# V3.net
KiCad netlist of a schematic drawn in Altium Designer
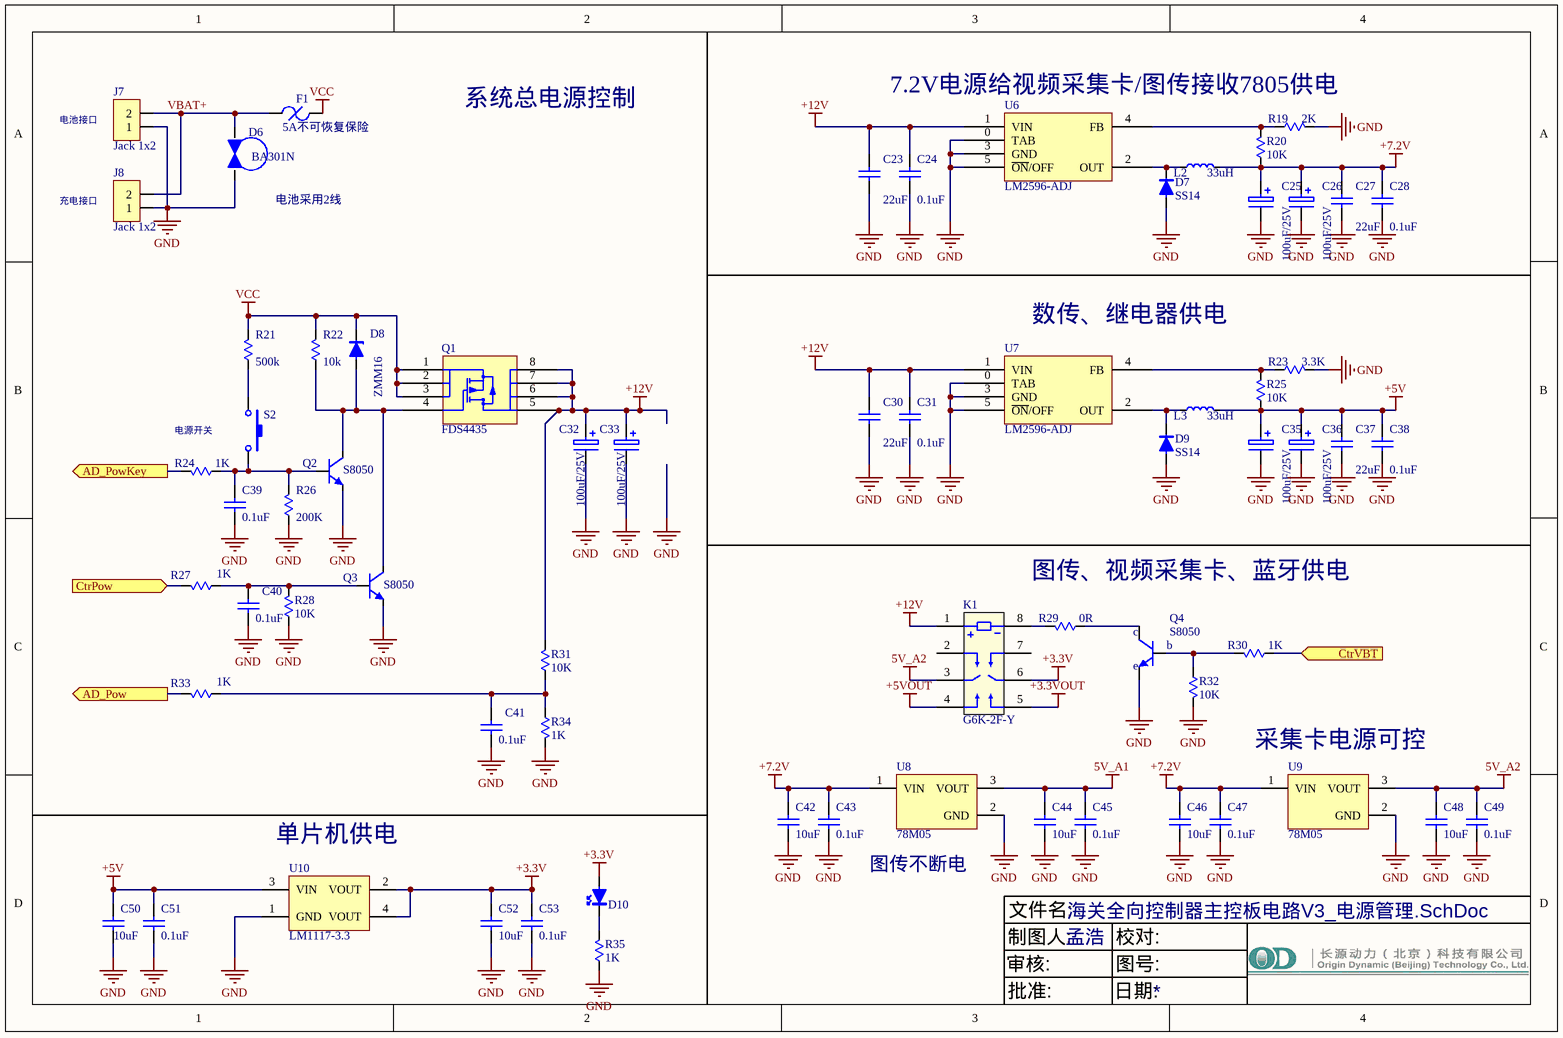
[diagram p0: 海关全向控制器主控板电路V3_电源管理.SchDoc]

(export (version "E")
  (design (tool "Eeschema 10.0.6"))
  (components
    (comp (ref "C23")
      (value "22uF")
      (footprint "C1210")
      (description "CAP")
      (fields (field (name "PUBLISHER") "Altium Limited"))
      (libsource (lib "Passive Components Class") (part "CAP"))
    )
    (comp (ref "C24")
      (value "0.1uF")
      (footprint "C0805")
      (description "CAP")
      (fields (field (name "PUBLISHER") "Altium Limited"))
      (libsource (lib "Passive Components Class") (part "CAP"))
    )
    (comp (ref "C25")
      (value "100uF/25V")
      (footprint "C7343")
      (description "Electrolytic Capacitor")
      (libsource (lib "*") (part "ELECTRO"))
    )
    (comp (ref "C26")
      (value "100uF/25V")
      (footprint "C7343")
      (description "Electrolytic Capacitor")
      (libsource (lib "*") (part "ELECTRO"))
    )
    (comp (ref "C27")
      (value "22uF")
      (footprint "C1210")
      (description "CAP")
      (fields (field (name "PUBLISHER") "Altium Limited"))
      (libsource (lib "Passive Components Class") (part "CAP"))
    )
    (comp (ref "C28")
      (value "0.1uF")
      (footprint "C0805")
      (description "CAP")
      (fields (field (name "PUBLISHER") "Altium Limited"))
      (libsource (lib "Passive Components Class") (part "CAP"))
    )
    (comp (ref "C30")
      (value "22uF")
      (footprint "C1210")
      (description "CAP")
      (fields (field (name "PUBLISHER") "Altium Limited"))
      (libsource (lib "Passive Components Class") (part "CAP"))
    )
    (comp (ref "C31")
      (value "0.1uF")
      (footprint "C0805")
      (description "CAP")
      (fields (field (name "PUBLISHER") "Altium Limited"))
      (libsource (lib "Passive Components Class") (part "CAP"))
    )
    (comp (ref "C32") (value "100uF/25V") (footprint "C7343") (libsource (lib "RLCYDF") (part "Cap Poll")))
    (comp (ref "C33") (value "100uF/25V") (footprint "C7343") (libsource (lib "RLCYDF") (part "Cap Poll")))
    (comp (ref "C35")
      (value "100uF/25V")
      (footprint "C7343")
      (description "Electrolytic Capacitor")
      (libsource (lib "*") (part "ELECTRO"))
    )
    (comp (ref "C36")
      (value "100uF/25V")
      (footprint "C7343")
      (description "Electrolytic Capacitor")
      (libsource (lib "*") (part "ELECTRO"))
    )
    (comp (ref "C37")
      (value "22uF")
      (footprint "C1210")
      (description "CAP")
      (fields (field (name "PUBLISHER") "Altium Limited"))
      (libsource (lib "Passive Components Class") (part "CAP"))
    )
    (comp (ref "C38")
      (value "0.1uF")
      (footprint "C0805")
      (description "CAP")
      (fields (field (name "PUBLISHER") "Altium Limited"))
      (libsource (lib "Passive Components Class") (part "CAP"))
    )
    (comp (ref "C39")
      (value "0.1uF")
      (footprint "C0805")
      (description "CAP")
      (fields (field (name "PUBLISHER") "Altium Limited"))
      (libsource (lib "Passive Components Class") (part "CAP"))
    )
    (comp (ref "C40")
      (value "0.1uF")
      (footprint "C0805")
      (description "CAP")
      (fields (field (name "PUBLISHER") "Altium Limited"))
      (libsource (lib "Passive Components Class") (part "CAP"))
    )
    (comp (ref "C41")
      (value "0.1uF")
      (footprint "C0805")
      (description "CAP")
      (fields (field (name "PUBLISHER") "Altium Limited"))
      (libsource (lib "Passive Components Class") (part "CAP"))
    )
    (comp (ref "C42")
      (value "10uF")
      (footprint "C0805")
      (description "CAP")
      (fields (field (name "PUBLISHER") "Altium Limited"))
      (libsource (lib "Passive Components Class") (part "CAP"))
    )
    (comp (ref "C43")
      (value "0.1uF")
      (footprint "C0805")
      (description "CAP")
      (fields (field (name "PUBLISHER") "Altium Limited"))
      (libsource (lib "Passive Components Class") (part "CAP"))
    )
    (comp (ref "C44")
      (value "10uF")
      (footprint "C0805")
      (description "CAP")
      (fields (field (name "PUBLISHER") "Altium Limited"))
      (libsource (lib "Passive Components Class") (part "CAP"))
    )
    (comp (ref "C45")
      (value "0.1uF")
      (footprint "C0805")
      (description "CAP")
      (fields (field (name "PUBLISHER") "Altium Limited"))
      (libsource (lib "Passive Components Class") (part "CAP"))
    )
    (comp (ref "C46")
      (value "10uF")
      (footprint "C0805")
      (description "CAP")
      (fields (field (name "PUBLISHER") "Altium Limited"))
      (libsource (lib "Passive Components Class") (part "CAP"))
    )
    (comp (ref "C47")
      (value "0.1uF")
      (footprint "C0805")
      (description "CAP")
      (fields (field (name "PUBLISHER") "Altium Limited"))
      (libsource (lib "Passive Components Class") (part "CAP"))
    )
    (comp (ref "C48")
      (value "10uF")
      (footprint "C0805")
      (description "CAP")
      (fields (field (name "PUBLISHER") "Altium Limited"))
      (libsource (lib "Passive Components Class") (part "CAP"))
    )
    (comp (ref "C49")
      (value "0.1uF")
      (footprint "C0805")
      (description "CAP")
      (fields (field (name "PUBLISHER") "Altium Limited"))
      (libsource (lib "Passive Components Class") (part "CAP"))
    )
    (comp (ref "C50")
      (value "10uF")
      (footprint "C0805")
      (description "CAP")
      (fields (field (name "PUBLISHER") "Altium Limited"))
      (libsource (lib "Passive Components Class") (part "CAP"))
    )
    (comp (ref "C51")
      (value "0.1uF")
      (footprint "C0805")
      (description "CAP")
      (fields (field (name "PUBLISHER") "Altium Limited"))
      (libsource (lib "Passive Components Class") (part "CAP"))
    )
    (comp (ref "C52")
      (value "10uF")
      (footprint "C0805")
      (description "CAP")
      (fields (field (name "PUBLISHER") "Altium Limited"))
      (libsource (lib "Passive Components Class") (part "CAP"))
    )
    (comp (ref "C53")
      (value "0.1uF")
      (footprint "C0805")
      (description "CAP")
      (fields (field (name "PUBLISHER") "Altium Limited"))
      (libsource (lib "Passive Components Class") (part "CAP"))
    )
    (comp (ref "D6") (value "BA301N") (footprint "BA301N") (libsource (lib "MhSchlib") (part "BA301N")))
    (comp (ref "D7")
      (value "SS14")
      (footprint "SMA")
      (description "Silicon Epitaxial Planar Diodes")
      (libsource (lib "RLCYDF") (part "Diode-Switch"))
    )
    (comp (ref "D8")
      (value "ZMM16")
      (footprint "SOD-80-S")
      (description "Small Signal Zener Diodes")
      (libsource (lib "Passive Components Class") (part "DIODE-ZENER"))
    )
    (comp (ref "D9")
      (value "SS14")
      (footprint "SMA")
      (description "Silicon Epitaxial Planar Diodes")
      (libsource (lib "RLCYDF") (part "Diode-Switch"))
    )
    (comp (ref "D10")
      (value "LED")
      (footprint "LED0603")
      (libsource (lib "Passive Components Class") (part "LED"))
    )
    (comp (ref "F1") (value "5A不可恢复保险") (footprint "F1808") (libsource (lib "RLCYDF") (part "Fuse2")))
    (comp (ref "J7")
      (value "Jack 1x2")
      (footprint "35363-0260")
      (description "插座")
      (libsource (lib "Connector") (part "Jack 1x2"))
    )
    (comp (ref "J8")
      (value "Jack 1x2")
      (footprint "35363-0260")
      (description "插座")
      (libsource (lib "Connector") (part "Jack 1x2"))
    )
    (comp (ref "K1")
      (value "G6K-2F-Y")
      (footprint "G6K-2F-Y")
      (libsource (lib "海关全向本体电路板V3") (part "G6K-2F-Y"))
    )
    (comp (ref "L2")
      (value "33uH")
      (footprint "L6.6*7.1mm")
      (description "INDUCTOR")
      (fields (field (name "PUBLISHER") "Altium Limited"))
      (libsource (lib "Passive Components Class") (part "INDUCTOR"))
    )
    (comp (ref "L3")
      (value "33uH")
      (footprint "L6.6*7.1mm")
      (description "INDUCTOR")
      (fields (field (name "PUBLISHER") "Altium Limited"))
      (libsource (lib "Passive Components Class") (part "INDUCTOR"))
    )
    (comp (ref "Q1") (value "FDS4435") (footprint "SO8") (libsource (lib "OmniDirCtr") (part "FDS4435")))
    (comp (ref "Q2")
      (value "S8050")
      (footprint "SOT-23")
      (description "NPN General Purpose Amplifier")
      (fields (field (name "PUBLISHER") "Altium Limited"))
      (libsource (lib "Bdmc4810") (part "NPN"))
    )
    (comp (ref "Q3")
      (value "S8050")
      (footprint "SOT-23")
      (description "NPN General Purpose Amplifier")
      (fields (field (name "PUBLISHER") "Altium Limited"))
      (libsource (lib "Bdmc4810") (part "NPN"))
    )
    (comp (ref "Q4")
      (value "S8050")
      (footprint "SOT-23")
      (description "NPN triode, 0.5A Max")
      (libsource (lib "RLCYDF") (part "S8050"))
    )
    (comp (ref "R19")
      (value "2K")
      (footprint "R0805")
      (description "Resistor")
      (fields (field (name "PUBLISHER") "Altium Limited"))
      (libsource (lib "Passive Components Class") (part "RES"))
    )
    (comp (ref "R20")
      (value "10K")
      (footprint "R0805")
      (description "Resistor")
      (fields (field (name "PUBLISHER") "Altium Limited"))
      (libsource (lib "Passive Components Class") (part "RES"))
    )
    (comp (ref "R21")
      (value "500k")
      (footprint "R0805")
      (description "Resistor")
      (fields (field (name "PUBLISHER") "Altium Limited"))
      (libsource (lib "Temp") (part "Res"))
    )
    (comp (ref "R22")
      (value "10k")
      (footprint "R0805")
      (description "Resistor")
      (fields (field (name "PUBLISHER") "Altium Limited"))
      (libsource (lib "Temp") (part "Res"))
    )
    (comp (ref "R23")
      (value "3.3K")
      (footprint "R0805")
      (description "Resistor")
      (fields (field (name "PUBLISHER") "Altium Limited"))
      (libsource (lib "Passive Components Class") (part "RES"))
    )
    (comp (ref "R24")
      (value "1K")
      (footprint "R0805")
      (description "Resistor")
      (fields (field (name "PUBLISHER") "Altium Limited"))
      (libsource (lib "Temp") (part "Res"))
    )
    (comp (ref "R25")
      (value "10K")
      (footprint "R0805")
      (description "Resistor")
      (fields (field (name "PUBLISHER") "Altium Limited"))
      (libsource (lib "Passive Components Class") (part "RES"))
    )
    (comp (ref "R26")
      (value "200K")
      (footprint "R0805")
      (description "Resistor")
      (fields (field (name "PUBLISHER") "Altium Limited"))
      (libsource (lib "Temp") (part "Res"))
    )
    (comp (ref "R27")
      (value "1K")
      (footprint "R0805")
      (description "Resistor")
      (fields (field (name "PUBLISHER") "Altium Limited"))
      (libsource (lib "Temp") (part "Res"))
    )
    (comp (ref "R28")
      (value "10K")
      (footprint "R0805")
      (description "Resistor")
      (fields (field (name "PUBLISHER") "Altium Limited"))
      (libsource (lib "Temp") (part "Res"))
    )
    (comp (ref "R29")
      (value "0R")
      (footprint "R0805")
      (description "Resistor")
      (fields (field (name "PUBLISHER") "Altium Limited"))
      (libsource (lib "Passive Components Class") (part "RES"))
    )
    (comp (ref "R30")
      (value "1K")
      (footprint "R0805")
      (description "Resistor")
      (fields (field (name "PUBLISHER") "Altium Limited"))
      (libsource (lib "Passive Components Class") (part "RES"))
    )
    (comp (ref "R31")
      (value "10K")
      (footprint "R0805")
      (description "Resistor")
      (fields (field (name "PUBLISHER") "Altium Limited"))
      (libsource (lib "Temp") (part "Res"))
    )
    (comp (ref "R32")
      (value "10K")
      (footprint "R0805")
      (description "Resistor")
      (fields (field (name "PUBLISHER") "Altium Limited"))
      (libsource (lib "Passive Components Class") (part "RES"))
    )
    (comp (ref "R33")
      (value "1K")
      (footprint "R0805")
      (description "Resistor")
      (fields (field (name "PUBLISHER") "Altium Limited"))
      (libsource (lib "Temp") (part "Res"))
    )
    (comp (ref "R34")
      (value "1K")
      (footprint "R0805")
      (description "Resistor")
      (fields (field (name "PUBLISHER") "Altium Limited"))
      (libsource (lib "Temp") (part "Res"))
    )
    (comp (ref "R35")
      (value "1K")
      (footprint "R0805")
      (description "Resistor")
      (fields (field (name "PUBLISHER") "Altium Limited"))
      (libsource (lib "UP-Robot") (part "Res"))
    )
    (comp (ref "S2")
      (value "SW-PB")
      (footprint "ZH-2AWD")
      (description "Switch")
      (fields (field (name "PUBLISHER") "Altium Limited"))
      (libsource (lib "海关全向控制器主控板V3") (part "SW-PB"))
    )
    (comp (ref "U6")
      (value "LM2596-ADJ")
      (footprint "TO-263-5")
      (description "LM2596-5;LM2576-5")
      (libsource (lib "chip") (part "LM25x6-5"))
    )
    (comp (ref "U7")
      (value "LM2596-ADJ")
      (footprint "TO-263-5")
      (description "LM2596-5;LM2576-5")
      (libsource (lib "chip") (part "LM25x6-5"))
    )
    (comp (ref "U8") (value "78M05") (footprint "TO-252") (libsource (lib "chip") (part "78M05")))
    (comp (ref "U9") (value "78M05") (footprint "TO-252") (libsource (lib "chip") (part "78M05")))
    (comp (ref "U10")
      (value "LM1117-3.3")
      (footprint "SOT-223")
      (description "800mA Linear Voltage Regulator")
      (libsource (lib "chip") (part "LM1117"))
    )
  )
  (nets
    (net (code "1") (name "+3.3V") (class "Default")
      (node (ref "C52") (pin "1") (pinfunction "1_1") (pintype "passive"))
      (node (ref "C53") (pin "2") (pinfunction "2_2") (pintype "passive"))
      (node (ref "D10") (pin "1") (pinfunction "A_1") (pintype "passive"))
      (node (ref "K1") (pin "6") (pinfunction "6_6") (pintype "passive"))
      (node (ref "U10") (pin "2") (pinfunction "VOUT_2") (pintype "passive"))
      (node (ref "U10") (pin "4") (pinfunction "VOUT_4") (pintype "passive"))
    )
    (net (code "2") (name "+3.3VOUT") (class "Default")
      (node (ref "K1") (pin "5") (pinfunction "5_5") (pintype "passive"))
    )
    (net (code "3") (name "+5V") (class "Default")
      (node (ref "C35") (pin "1") (pinfunction "1_1") (pintype "passive"))
      (node (ref "C36") (pin "1") (pinfunction "1_1") (pintype "passive"))
      (node (ref "C37") (pin "1") (pinfunction "1_1") (pintype "passive"))
      (node (ref "C38") (pin "2") (pinfunction "2_2") (pintype "passive"))
      (node (ref "C50") (pin "1") (pinfunction "1_1") (pintype "passive"))
      (node (ref "C51") (pin "2") (pinfunction "2_2") (pintype "passive"))
      (node (ref "L3") (pin "2") (pinfunction "2_2") (pintype "passive"))
      (node (ref "R25") (pin "1") (pinfunction "1_1") (pintype "passive"))
      (node (ref "U10") (pin "3") (pinfunction "VIN_3") (pintype "passive"))
    )
    (net (code "4") (name "+5VOUT") (class "Default")
      (node (ref "K1") (pin "4") (pinfunction "4_4") (pintype "passive"))
    )
    (net (code "5") (name "+7.2V") (class "Default")
      (node (ref "C25") (pin "1") (pinfunction "1_1") (pintype "passive"))
      (node (ref "C26") (pin "1") (pinfunction "1_1") (pintype "passive"))
      (node (ref "C27") (pin "1") (pinfunction "1_1") (pintype "passive"))
      (node (ref "C28") (pin "2") (pinfunction "2_2") (pintype "passive"))
      (node (ref "C42") (pin "1") (pinfunction "1_1") (pintype "passive"))
      (node (ref "C43") (pin "2") (pinfunction "2_2") (pintype "passive"))
      (node (ref "C46") (pin "1") (pinfunction "1_1") (pintype "passive"))
      (node (ref "C47") (pin "2") (pinfunction "2_2") (pintype "passive"))
      (node (ref "L2") (pin "2") (pinfunction "2_2") (pintype "passive"))
      (node (ref "R20") (pin "1") (pinfunction "1_1") (pintype "passive"))
      (node (ref "U8") (pin "1") (pinfunction "VIN_1") (pintype "passive"))
      (node (ref "U9") (pin "1") (pinfunction "VIN_1") (pintype "passive"))
    )
    (net (code "6") (name "+12V") (class "Default")
      (node (ref "C23") (pin "1") (pinfunction "1_1") (pintype "passive"))
      (node (ref "C24") (pin "2") (pinfunction "2_2") (pintype "passive"))
      (node (ref "C30") (pin "1") (pinfunction "1_1") (pintype "passive"))
      (node (ref "C31") (pin "2") (pinfunction "2_2") (pintype "passive"))
      (node (ref "C32") (pin "1") (pinfunction "1_1") (pintype "passive"))
      (node (ref "C33") (pin "1") (pinfunction "1_1") (pintype "passive"))
      (node (ref "K1") (pin "1") (pinfunction "1_1") (pintype "passive"))
      (node (ref "Q1") (pin "5") (pintype "passive"))
      (node (ref "Q1") (pin "6") (pintype "passive"))
      (node (ref "Q1") (pin "7") (pintype "passive"))
      (node (ref "Q1") (pin "8") (pintype "passive"))
      (node (ref "R31") (pin "1") (pinfunction "1_1") (pintype "passive"))
      (node (ref "U6") (pin "1") (pinfunction "VIN_1") (pintype "passive"))
      (node (ref "U7") (pin "1") (pinfunction "VIN_1") (pintype "passive"))
    )
    (net (code "7") (name "/AD_Pow") (class "Default")
      (node (ref "R33") (pin "1") (pinfunction "1_1") (pintype "passive"))
    )
    (net (code "8") (name "/AD_PowKey") (class "Default")
      (node (ref "R24") (pin "1") (pinfunction "1_1") (pintype "passive"))
    )
    (net (code "9") (name "/CtrPow") (class "Default")
      (node (ref "R27") (pin "1") (pinfunction "1_1") (pintype "passive"))
    )
    (net (code "10") (name "/CtrVBT") (class "Default")
      (node (ref "R30") (pin "1") (pinfunction "1_1") (pintype "passive"))
    )
    (net (code "11") (name "/VBAT+") (class "Default")
      (node (ref "D6") (pin "1") (pinfunction "1_1") (pintype "passive"))
      (node (ref "F1") (pin "1") (pinfunction "1_1") (pintype "passive"))
      (node (ref "J7") (pin "2") (pinfunction "2_2") (pintype "passive"))
      (node (ref "J8") (pin "2") (pinfunction "2_2") (pintype "passive"))
    )
    (net (code "12") (name "5V_A1") (class "Default")
      (node (ref "C44") (pin "1") (pinfunction "1_1") (pintype "passive"))
      (node (ref "C45") (pin "2") (pinfunction "2_2") (pintype "passive"))
      (node (ref "U8") (pin "3") (pinfunction "VOUT_3") (pintype "passive"))
    )
    (net (code "13") (name "5V_A2") (class "Default")
      (node (ref "C48") (pin "1") (pinfunction "1_1") (pintype "passive"))
      (node (ref "C49") (pin "2") (pinfunction "2_2") (pintype "passive"))
      (node (ref "K1") (pin "3") (pinfunction "3_3") (pintype "passive"))
      (node (ref "U9") (pin "3") (pinfunction "VOUT_3") (pintype "passive"))
    )
    (net (code "14") (name "GND") (class "Default")
      (node (ref "C23") (pin "2") (pinfunction "2_2") (pintype "passive"))
      (node (ref "C24") (pin "1") (pinfunction "1_1") (pintype "passive"))
      (node (ref "C25") (pin "2") (pinfunction "2_2") (pintype "passive"))
      (node (ref "C26") (pin "2") (pinfunction "2_2") (pintype "passive"))
      (node (ref "C27") (pin "2") (pinfunction "2_2") (pintype "passive"))
      (node (ref "C28") (pin "1") (pinfunction "1_1") (pintype "passive"))
      (node (ref "C30") (pin "2") (pinfunction "2_2") (pintype "passive"))
      (node (ref "C31") (pin "1") (pinfunction "1_1") (pintype "passive"))
      (node (ref "C32") (pin "2") (pinfunction "2_2") (pintype "passive"))
      (node (ref "C33") (pin "2") (pinfunction "2_2") (pintype "passive"))
      (node (ref "C35") (pin "2") (pinfunction "2_2") (pintype "passive"))
      (node (ref "C36") (pin "2") (pinfunction "2_2") (pintype "passive"))
      (node (ref "C37") (pin "2") (pinfunction "2_2") (pintype "passive"))
      (node (ref "C38") (pin "1") (pinfunction "1_1") (pintype "passive"))
      (node (ref "C39") (pin "1") (pinfunction "1_1") (pintype "passive"))
      (node (ref "C40") (pin "1") (pinfunction "1_1") (pintype "passive"))
      (node (ref "C41") (pin "1") (pinfunction "1_1") (pintype "passive"))
      (node (ref "C42") (pin "2") (pinfunction "2_2") (pintype "passive"))
      (node (ref "C43") (pin "1") (pinfunction "1_1") (pintype "passive"))
      (node (ref "C44") (pin "2") (pinfunction "2_2") (pintype "passive"))
      (node (ref "C45") (pin "1") (pinfunction "1_1") (pintype "passive"))
      (node (ref "C46") (pin "2") (pinfunction "2_2") (pintype "passive"))
      (node (ref "C47") (pin "1") (pinfunction "1_1") (pintype "passive"))
      (node (ref "C48") (pin "2") (pinfunction "2_2") (pintype "passive"))
      (node (ref "C49") (pin "1") (pinfunction "1_1") (pintype "passive"))
      (node (ref "C50") (pin "2") (pinfunction "2_2") (pintype "passive"))
      (node (ref "C51") (pin "1") (pinfunction "1_1") (pintype "passive"))
      (node (ref "C52") (pin "2") (pinfunction "2_2") (pintype "passive"))
      (node (ref "C53") (pin "1") (pinfunction "1_1") (pintype "passive"))
      (node (ref "D6") (pin "2") (pinfunction "2_2") (pintype "passive"))
      (node (ref "D7") (pin "1") (pinfunction "A_1") (pintype "passive"))
      (node (ref "D9") (pin "1") (pinfunction "A_1") (pintype "passive"))
      (node (ref "J7") (pin "1") (pinfunction "1_1") (pintype "passive"))
      (node (ref "J8") (pin "1") (pinfunction "1_1") (pintype "passive"))
      (node (ref "Q2") (pin "2") (pinfunction "E_2") (pintype "passive"))
      (node (ref "Q3") (pin "2") (pinfunction "E_2") (pintype "passive"))
      (node (ref "Q4") (pin "2") (pinfunction "e_2") (pintype "passive"))
      (node (ref "R19") (pin "2") (pinfunction "2_2") (pintype "passive"))
      (node (ref "R23") (pin "2") (pinfunction "2_2") (pintype "passive"))
      (node (ref "R26") (pin "2") (pinfunction "2_2") (pintype "passive"))
      (node (ref "R28") (pin "2") (pinfunction "2_2") (pintype "passive"))
      (node (ref "R32") (pin "2") (pinfunction "2_2") (pintype "passive"))
      (node (ref "R34") (pin "1") (pinfunction "1_1") (pintype "passive"))
      (node (ref "R35") (pin "1") (pinfunction "1_1") (pintype "passive"))
      (node (ref "U10") (pin "1") (pinfunction "GND_1") (pintype "passive"))
      (node (ref "U6") (pin "0") (pinfunction "TAB_0") (pintype "passive"))
      (node (ref "U6") (pin "3") (pinfunction "GND_3") (pintype "passive"))
      (node (ref "U6") (pin "5") (pinfunction "~{ON}/OFF_5") (pintype "passive"))
      (node (ref "U7") (pin "0") (pinfunction "TAB_0") (pintype "passive"))
      (node (ref "U7") (pin "3") (pinfunction "GND_3") (pintype "passive"))
      (node (ref "U7") (pin "5") (pinfunction "~{ON}/OFF_5") (pintype "passive"))
      (node (ref "U8") (pin "2") (pinfunction "GND_2") (pintype "passive"))
      (node (ref "U9") (pin "2") (pinfunction "GND_2") (pintype "passive"))
    )
    (net (code "15") (name "Net-(C41-Pad2)") (class "Default")
      (node (ref "C41") (pin "2") (pinfunction "2_2") (pintype "passive"))
      (node (ref "R31") (pin "2") (pinfunction "2_2") (pintype "passive"))
      (node (ref "R33") (pin "2") (pinfunction "2_2") (pintype "passive"))
      (node (ref "R34") (pin "2") (pinfunction "2_2") (pintype "passive"))
    )
    (net (code "16") (name "Net-(D7-K)") (class "Default")
      (node (ref "D7") (pin "2") (pinfunction "K_2") (pintype "passive"))
      (node (ref "L2") (pin "1") (pinfunction "1_1") (pintype "passive"))
      (node (ref "U6") (pin "2") (pinfunction "OUT_2") (pintype "passive"))
    )
    (net (code "17") (name "Net-(D8-A)") (class "Default")
      (node (ref "D8") (pin "1") (pinfunction "A_1") (pintype "passive"))
      (node (ref "Q1") (pin "4") (pintype "passive"))
      (node (ref "Q2") (pin "3") (pinfunction "C_3") (pintype "passive"))
      (node (ref "Q3") (pin "3") (pinfunction "C_3") (pintype "passive"))
      (node (ref "R22") (pin "1") (pinfunction "1_1") (pintype "passive"))
    )
    (net (code "18") (name "Net-(D9-K)") (class "Default")
      (node (ref "D9") (pin "2") (pinfunction "K_2") (pintype "passive"))
      (node (ref "L3") (pin "1") (pinfunction "1_1") (pintype "passive"))
      (node (ref "U7") (pin "2") (pinfunction "OUT_2") (pintype "passive"))
    )
    (net (code "19") (name "Net-(D10-K)") (class "Default")
      (node (ref "D10") (pin "2") (pinfunction "K_2") (pintype "passive"))
      (node (ref "R35") (pin "2") (pinfunction "2_2") (pintype "passive"))
    )
    (net (code "20") (name "Net-(K1-Pad8)") (class "Default")
      (node (ref "K1") (pin "8") (pinfunction "8_8") (pintype "passive"))
      (node (ref "R29") (pin "2") (pinfunction "2_2") (pintype "passive"))
    )
    (net (code "21") (name "Net-(Q2-B)") (class "Default")
      (node (ref "C39") (pin "2") (pinfunction "2_2") (pintype "passive"))
      (node (ref "Q2") (pin "1") (pinfunction "B_1") (pintype "passive"))
      (node (ref "R24") (pin "2") (pinfunction "2_2") (pintype "passive"))
      (node (ref "R26") (pin "1") (pinfunction "1_1") (pintype "passive"))
      (node (ref "S2") (pin "2") (pinfunction "2_2") (pintype "passive"))
    )
    (net (code "22") (name "Net-(Q3-B)") (class "Default")
      (node (ref "C40") (pin "2") (pinfunction "2_2") (pintype "passive"))
      (node (ref "Q3") (pin "1") (pinfunction "B_1") (pintype "passive"))
      (node (ref "R27") (pin "2") (pinfunction "2_2") (pintype "passive"))
      (node (ref "R28") (pin "1") (pinfunction "1_1") (pintype "passive"))
    )
    (net (code "23") (name "Net-(Q4-b)") (class "Default")
      (node (ref "Q4") (pin "1") (pinfunction "b_1") (pintype "passive"))
      (node (ref "R30") (pin "2") (pinfunction "2_2") (pintype "passive"))
      (node (ref "R32") (pin "1") (pinfunction "1_1") (pintype "passive"))
    )
    (net (code "24") (name "Net-(Q4-c)") (class "Default")
      (node (ref "Q4") (pin "3") (pinfunction "c_3") (pintype "passive"))
      (node (ref "R29") (pin "1") (pinfunction "1_1") (pintype "passive"))
    )
    (net (code "25") (name "Net-(R21-Pad1)") (class "Default")
      (node (ref "R21") (pin "1") (pinfunction "1_1") (pintype "passive"))
      (node (ref "S2") (pin "1") (pinfunction "1_1") (pintype "passive"))
    )
    (net (code "26") (name "Net-(U6-FB)") (class "Default")
      (node (ref "R19") (pin "1") (pinfunction "1_1") (pintype "passive"))
      (node (ref "R20") (pin "2") (pinfunction "2_2") (pintype "passive"))
      (node (ref "U6") (pin "4") (pinfunction "FB_4") (pintype "passive"))
    )
    (net (code "27") (name "Net-(U7-FB)") (class "Default")
      (node (ref "R23") (pin "1") (pinfunction "1_1") (pintype "passive"))
      (node (ref "R25") (pin "2") (pinfunction "2_2") (pintype "passive"))
      (node (ref "U7") (pin "4") (pinfunction "FB_4") (pintype "passive"))
    )
    (net (code "28") (name "VCC") (class "Default")
      (node (ref "D8") (pin "2") (pinfunction "K_2") (pintype "passive"))
      (node (ref "F1") (pin "2") (pinfunction "2_2") (pintype "passive"))
      (node (ref "Q1") (pin "1") (pintype "passive"))
      (node (ref "Q1") (pin "2") (pintype "passive"))
      (node (ref "Q1") (pin "3") (pintype "passive"))
      (node (ref "R21") (pin "2") (pinfunction "2_2") (pintype "passive"))
      (node (ref "R22") (pin "2") (pinfunction "2_2") (pintype "passive"))
    )
    (net (code "29") (name "unconnected-(K1-Pad2)") (class "Default")
      (node (ref "K1") (pin "2") (pinfunction "2_2") (pintype "passive"))
    )
    (net (code "30") (name "unconnected-(K1-Pad7)") (class "Default")
      (node (ref "K1") (pin "7") (pinfunction "7_7") (pintype "passive"))
    )
  )
)
